# FMC_and_Power.net
KiCad netlist of a schematic drawn in Altium Designer
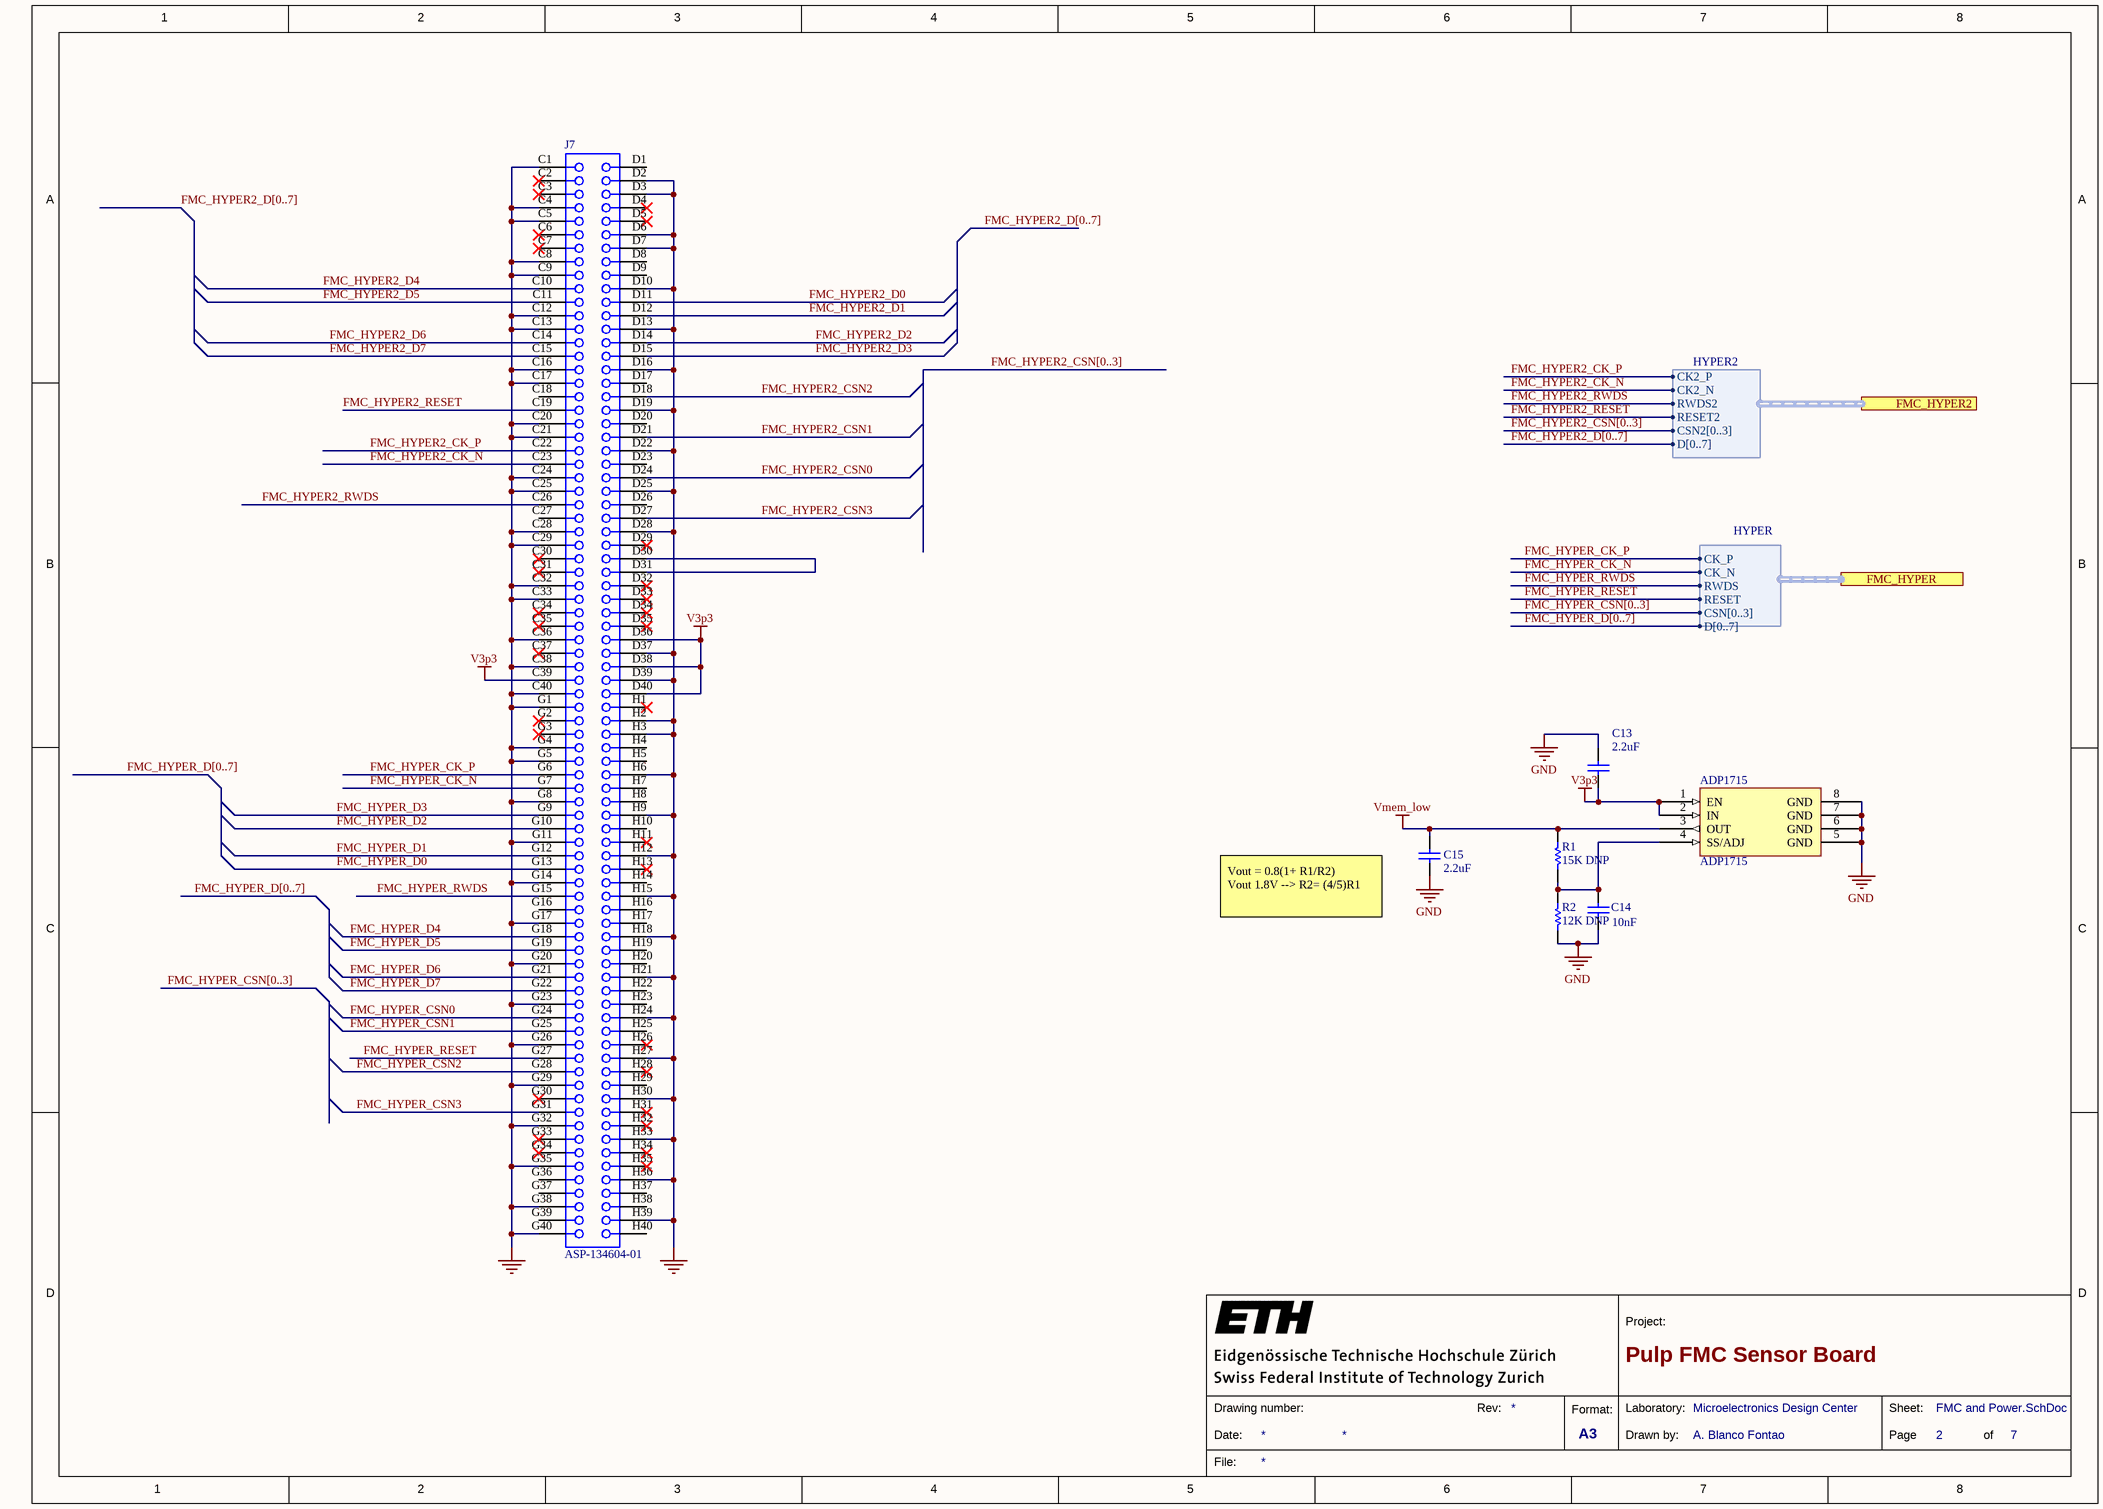
[diagram p0: FMC and Power.SchDoc]

(export (version "E")
  (design (tool "Eeschema 10.0.6"))
  (components
    (comp (ref "ADP1715")
      (value "ADP1715")
      (footprint "TSOP65P490X110-8N")
      (libsource (lib "ADP1715") (part "ADP1715"))
    )
    (comp (ref "C13")
      (value "2.2uF")
      (footprint "0402-A")
      (description "Capacitor (Semiconductor SIM Model)")
      (fields (field (name "Comment") "Cap Semi") (field (name "PUBLISHER") "Altium Limited"))
      (libsource (lib "Miscellaneous Devices") (part "Cap Semi"))
    )
    (comp (ref "C14")
      (value "10nF")
      (footprint "0402-A")
      (description "Capacitor (Semiconductor SIM Model)")
      (fields (field (name "Comment") "Cap Semi") (field (name "PUBLISHER") "Altium Limited"))
      (libsource (lib "Miscellaneous Devices") (part "Cap Semi"))
    )
    (comp (ref "C15")
      (value "2.2uF")
      (footprint "0402-A")
      (description "Capacitor (Semiconductor SIM Model)")
      (fields (field (name "Comment") "Cap Semi") (field (name "PUBLISHER") "Altium Limited"))
      (libsource (lib "Miscellaneous Devices") (part "Cap Semi"))
    )
    (comp (ref "J7")
      (value "ASP-134604-01")
      (footprint "ASP-134604-01")
      (description "Conn Array Terminal FMC Male SKT 160 POS 1.27mm Solder ST SMD")
      (fields (field (name "MANUFACTURER") "Samtec"))
      (libsource (lib "ETHZ Vault") (part "ASP-134604-01"))
    )
    (comp (ref "R1")
      (value "15K DNP")
      (footprint "RESC0603(1608)_N")
      (description "15K 0.1W 5% 0603 (1608 Metric)  SMD")
      (fields (field (name "TOLERANCE") "5 %") (field (name "POWER") "0.1 W"))
      (libsource (lib "Altium Content Vault") (part "CMP-1012-00098-1"))
    )
    (comp (ref "R2")
      (value "12K DNP")
      (footprint "RESC0603(1608)_N")
      (description "12K 0.1W 5% 0603 (1608 Metric)  SMD")
      (fields (field (name "TOLERANCE") "5 %") (field (name "POWER") "0.1 W"))
      (libsource (lib "Altium Content Vault") (part "CMP-1012-00098-1"))
    )
  )
  (nets
    (net (code "3") (name "/FMC_HYPER2_CK_N") (class "Default")
      (node (ref "J7") (pin "C23") (pinfunction "C23_C23") (pintype "passive"))
    )
    (net (code "4") (name "/FMC_HYPER2_CK_P") (class "Default")
      (node (ref "J7") (pin "C22") (pinfunction "C22_C22") (pintype "passive"))
    )
    (net (code "5") (name "/FMC_HYPER2_CSN0") (class "Default")
      (node (ref "J7") (pin "D24") (pinfunction "D24_D24") (pintype "passive"))
    )
    (net (code "6") (name "/FMC_HYPER2_CSN1") (class "Default")
      (node (ref "J7") (pin "D21") (pinfunction "D21_D21") (pintype "passive"))
    )
    (net (code "7") (name "/FMC_HYPER2_CSN2") (class "Default")
      (node (ref "J7") (pin "D18") (pinfunction "D18_D18") (pintype "passive"))
    )
    (net (code "8") (name "/FMC_HYPER2_CSN3") (class "Default")
      (node (ref "J7") (pin "D27") (pinfunction "D27_D27") (pintype "passive"))
    )
    (net (code "10") (name "/FMC_HYPER2_D0") (class "Default")
      (node (ref "J7") (pin "D11") (pinfunction "D11_D11") (pintype "passive"))
    )
    (net (code "11") (name "/FMC_HYPER2_D1") (class "Default")
      (node (ref "J7") (pin "D12") (pinfunction "D12_D12") (pintype "passive"))
    )
    (net (code "12") (name "/FMC_HYPER2_D2") (class "Default")
      (node (ref "J7") (pin "D14") (pinfunction "D14_D14") (pintype "passive"))
    )
    (net (code "13") (name "/FMC_HYPER2_D3") (class "Default")
      (node (ref "J7") (pin "D15") (pinfunction "D15_D15") (pintype "passive"))
    )
    (net (code "14") (name "/FMC_HYPER2_D4") (class "Default")
      (node (ref "J7") (pin "C10") (pinfunction "C10_C10") (pintype "passive"))
    )
    (net (code "15") (name "/FMC_HYPER2_D5") (class "Default")
      (node (ref "J7") (pin "C11") (pinfunction "C11_C11") (pintype "passive"))
    )
    (net (code "16") (name "/FMC_HYPER2_D6") (class "Default")
      (node (ref "J7") (pin "C14") (pinfunction "C14_C14") (pintype "passive"))
    )
    (net (code "17") (name "/FMC_HYPER2_D7") (class "Default")
      (node (ref "J7") (pin "C15") (pinfunction "C15_C15") (pintype "passive"))
    )
    (net (code "19") (name "/FMC_HYPER2_RESET") (class "Default")
      (node (ref "J7") (pin "C19") (pinfunction "C19_C19") (pintype "passive"))
    )
    (net (code "20") (name "/FMC_HYPER2_RWDS") (class "Default")
      (node (ref "J7") (pin "C26") (pinfunction "C26_C26") (pintype "passive"))
    )
    (net (code "22") (name "/FMC_HYPER_CK_N") (class "Default")
      (node (ref "J7") (pin "G7") (pinfunction "G7_G7") (pintype "passive"))
    )
    (net (code "23") (name "/FMC_HYPER_CK_P") (class "Default")
      (node (ref "J7") (pin "G6") (pinfunction "G6_G6") (pintype "passive"))
    )
    (net (code "24") (name "/FMC_HYPER_CSN0") (class "Default")
      (node (ref "J7") (pin "G24") (pinfunction "G24_G24") (pintype "passive"))
    )
    (net (code "25") (name "/FMC_HYPER_CSN1") (class "Default")
      (node (ref "J7") (pin "G25") (pinfunction "G25_G25") (pintype "passive"))
    )
    (net (code "26") (name "/FMC_HYPER_CSN2") (class "Default")
      (node (ref "J7") (pin "G28") (pinfunction "G28_G28") (pintype "passive"))
    )
    (net (code "27") (name "/FMC_HYPER_CSN3") (class "Default")
      (node (ref "J7") (pin "G31") (pinfunction "G31_G31") (pintype "passive"))
    )
    (net (code "29") (name "/FMC_HYPER_D0") (class "Default")
      (node (ref "J7") (pin "G13") (pinfunction "G13_G13") (pintype "passive"))
    )
    (net (code "30") (name "/FMC_HYPER_D1") (class "Default")
      (node (ref "J7") (pin "G12") (pinfunction "G12_G12") (pintype "passive"))
    )
    (net (code "31") (name "/FMC_HYPER_D2") (class "Default")
      (node (ref "J7") (pin "G10") (pinfunction "G10_G10") (pintype "passive"))
    )
    (net (code "32") (name "/FMC_HYPER_D3") (class "Default")
      (node (ref "J7") (pin "G9") (pinfunction "G9_G9") (pintype "passive"))
    )
    (net (code "33") (name "/FMC_HYPER_D4") (class "Default")
      (node (ref "J7") (pin "G18") (pinfunction "G18_G18") (pintype "passive"))
    )
    (net (code "34") (name "/FMC_HYPER_D5") (class "Default")
      (node (ref "J7") (pin "G19") (pinfunction "G19_G19") (pintype "passive"))
    )
    (net (code "35") (name "/FMC_HYPER_D6") (class "Default")
      (node (ref "J7") (pin "G21") (pinfunction "G21_G21") (pintype "passive"))
    )
    (net (code "36") (name "/FMC_HYPER_D7") (class "Default")
      (node (ref "J7") (pin "G22") (pinfunction "G22_G22") (pintype "passive"))
    )
    (net (code "38") (name "/FMC_HYPER_RESET") (class "Default")
      (node (ref "J7") (pin "G27") (pinfunction "G27_G27") (pintype "passive"))
    )
    (net (code "39") (name "/FMC_HYPER_RWDS") (class "Default")
      (node (ref "J7") (pin "G15") (pinfunction "G15_G15") (pintype "passive"))
    )
    (net (code "43") (name "GND") (class "Default")
      (node (ref "ADP1715") (pin "5") (pinfunction "GND_5") (pintype "power_in"))
      (node (ref "ADP1715") (pin "6") (pinfunction "GND_6") (pintype "power_in"))
      (node (ref "ADP1715") (pin "7") (pinfunction "GND_7") (pintype "power_in"))
      (node (ref "ADP1715") (pin "8") (pinfunction "GND_8") (pintype "power_in"))
      (node (ref "C13") (pin "1") (pinfunction "1_1") (pintype "passive"))
      (node (ref "C14") (pin "2") (pinfunction "2_2") (pintype "passive"))
      (node (ref "C15") (pin "2") (pinfunction "2_2") (pintype "passive"))
      (node (ref "J7") (pin "C1") (pinfunction "C1_C1") (pintype "passive"))
      (node (ref "J7") (pin "C12") (pinfunction "C12_C12") (pintype "passive"))
      (node (ref "J7") (pin "C13") (pinfunction "C13_C13") (pintype "passive"))
      (node (ref "J7") (pin "C16") (pinfunction "C16_C16") (pintype "passive"))
      (node (ref "J7") (pin "C17") (pinfunction "C17_C17") (pintype "passive"))
      (node (ref "J7") (pin "C20") (pinfunction "C20_C20") (pintype "passive"))
      (node (ref "J7") (pin "C21") (pinfunction "C21_C21") (pintype "passive"))
      (node (ref "J7") (pin "C24") (pinfunction "C24_C24") (pintype "passive"))
      (node (ref "J7") (pin "C25") (pinfunction "C25_C25") (pintype "passive"))
      (node (ref "J7") (pin "C28") (pinfunction "C28_C28") (pintype "passive"))
      (node (ref "J7") (pin "C29") (pinfunction "C29_C29") (pintype "passive"))
      (node (ref "J7") (pin "C32") (pinfunction "C32_C32") (pintype "passive"))
      (node (ref "J7") (pin "C33") (pinfunction "C33_C33") (pintype "passive"))
      (node (ref "J7") (pin "C36") (pinfunction "C36_C36") (pintype "passive"))
      (node (ref "J7") (pin "C38") (pinfunction "C38_C38") (pintype "passive"))
      (node (ref "J7") (pin "C4") (pinfunction "C4_C4") (pintype "passive"))
      (node (ref "J7") (pin "C40") (pinfunction "C40_C40") (pintype "passive"))
      (node (ref "J7") (pin "C5") (pinfunction "C5_C5") (pintype "passive"))
      (node (ref "J7") (pin "C8") (pinfunction "C8_C8") (pintype "passive"))
      (node (ref "J7") (pin "C9") (pinfunction "C9_C9") (pintype "passive"))
      (node (ref "J7") (pin "D10") (pinfunction "D10_D10") (pintype "passive"))
      (node (ref "J7") (pin "D13") (pinfunction "D13_D13") (pintype "passive"))
      (node (ref "J7") (pin "D16") (pinfunction "D16_D16") (pintype "passive"))
      (node (ref "J7") (pin "D19") (pinfunction "D19_D19") (pintype "passive"))
      (node (ref "J7") (pin "D2") (pinfunction "D2_D2") (pintype "passive"))
      (node (ref "J7") (pin "D22") (pinfunction "D22_D22") (pintype "passive"))
      (node (ref "J7") (pin "D25") (pinfunction "D25_D25") (pintype "passive"))
      (node (ref "J7") (pin "D28") (pinfunction "D28_D28") (pintype "passive"))
      (node (ref "J7") (pin "D3") (pinfunction "D3_D3") (pintype "passive"))
      (node (ref "J7") (pin "D37") (pinfunction "D37_D37") (pintype "passive"))
      (node (ref "J7") (pin "D39") (pinfunction "D39_D39") (pintype "passive"))
      (node (ref "J7") (pin "D6") (pinfunction "D6_D6") (pintype "passive"))
      (node (ref "J7") (pin "D7") (pinfunction "D7_D7") (pintype "passive"))
      (node (ref "J7") (pin "G1") (pinfunction "G1_G1") (pintype "passive"))
      (node (ref "J7") (pin "G11") (pinfunction "G11_G11") (pintype "passive"))
      (node (ref "J7") (pin "G14") (pinfunction "G14_G14") (pintype "passive"))
      (node (ref "J7") (pin "G17") (pinfunction "G17_G17") (pintype "passive"))
      (node (ref "J7") (pin "G20") (pinfunction "G20_G20") (pintype "passive"))
      (node (ref "J7") (pin "G23") (pinfunction "G23_G23") (pintype "passive"))
      (node (ref "J7") (pin "G26") (pinfunction "G26_G26") (pintype "passive"))
      (node (ref "J7") (pin "G29") (pinfunction "G29_G29") (pintype "passive"))
      (node (ref "J7") (pin "G32") (pinfunction "G32_G32") (pintype "passive"))
      (node (ref "J7") (pin "G35") (pinfunction "G35_G35") (pintype "passive"))
      (node (ref "J7") (pin "G38") (pinfunction "G38_G38") (pintype "passive"))
      (node (ref "J7") (pin "G4") (pinfunction "G4_G4") (pintype "passive"))
      (node (ref "J7") (pin "G40") (pinfunction "G40_G40") (pintype "passive"))
      (node (ref "J7") (pin "G5") (pinfunction "G5_G5") (pintype "passive"))
      (node (ref "J7") (pin "G8") (pinfunction "G8_G8") (pintype "passive"))
      (node (ref "J7") (pin "H12") (pinfunction "H12_H12") (pintype "passive"))
      (node (ref "J7") (pin "H15") (pinfunction "H15_H15") (pintype "passive"))
      (node (ref "J7") (pin "H18") (pinfunction "H18_H18") (pintype "passive"))
      (node (ref "J7") (pin "H2") (pinfunction "H2_H2") (pintype "passive"))
      (node (ref "J7") (pin "H21") (pinfunction "H21_H21") (pintype "passive"))
      (node (ref "J7") (pin "H24") (pinfunction "H24_H24") (pintype "passive"))
      (node (ref "J7") (pin "H27") (pinfunction "H27_H27") (pintype "passive"))
      (node (ref "J7") (pin "H3") (pinfunction "H3_H3") (pintype "passive"))
      (node (ref "J7") (pin "H30") (pinfunction "H30_H30") (pintype "passive"))
      (node (ref "J7") (pin "H33") (pinfunction "H33_H33") (pintype "passive"))
      (node (ref "J7") (pin "H36") (pinfunction "H36_H36") (pintype "passive"))
      (node (ref "J7") (pin "H39") (pinfunction "H39_H39") (pintype "passive"))
      (node (ref "J7") (pin "H6") (pinfunction "H6_H6") (pintype "passive"))
      (node (ref "J7") (pin "H9") (pinfunction "H9_H9") (pintype "passive"))
      (node (ref "R2") (pin "1") (pinfunction "1_1") (pintype "passive"))
    )
    (net (code "44") (name "Net-(ADP1715-SS{slash}ADJ)") (class "Default")
      (node (ref "ADP1715") (pin "4") (pinfunction "SS/ADJ_4") (pintype "input"))
      (node (ref "C14") (pin "1") (pinfunction "1_1") (pintype "passive"))
      (node (ref "R1") (pin "1") (pinfunction "1_1") (pintype "passive"))
      (node (ref "R2") (pin "2") (pinfunction "2_2") (pintype "passive"))
    )
    (net (code "45") (name "Net-(J7-PadD30)") (class "Default")
      (node (ref "J7") (pin "D30") (pinfunction "D30_D30") (pintype "passive"))
      (node (ref "J7") (pin "D31") (pinfunction "D31_D31") (pintype "passive"))
    )
    (net (code "46") (name "V3p3") (class "Default")
      (node (ref "ADP1715") (pin "1") (pinfunction "EN_1") (pintype "input"))
      (node (ref "ADP1715") (pin "2") (pinfunction "IN_2") (pintype "input"))
      (node (ref "C13") (pin "2") (pinfunction "2_2") (pintype "passive"))
      (node (ref "J7") (pin "C39") (pinfunction "C39_C39") (pintype "passive"))
      (node (ref "J7") (pin "D36") (pinfunction "D36_D36") (pintype "passive"))
      (node (ref "J7") (pin "D38") (pinfunction "D38_D38") (pintype "passive"))
      (node (ref "J7") (pin "D40") (pinfunction "D40_D40") (pintype "passive"))
    )
    (net (code "47") (name "Vmem_low") (class "Default")
      (node (ref "ADP1715") (pin "3") (pinfunction "OUT_3") (pintype "output"))
      (node (ref "C15") (pin "1") (pinfunction "1_1") (pintype "passive"))
      (node (ref "R1") (pin "2") (pinfunction "2_2") (pintype "passive"))
    )
    (net (code "48") (name "unconnected-(J7-PadC2)") (class "Default")
      (node (ref "J7") (pin "C2") (pinfunction "C2_C2") (pintype "passive+no_connect"))
    )
    (net (code "49") (name "unconnected-(J7-PadC3)") (class "Default")
      (node (ref "J7") (pin "C3") (pinfunction "C3_C3") (pintype "passive+no_connect"))
    )
    (net (code "50") (name "unconnected-(J7-PadC6)") (class "Default")
      (node (ref "J7") (pin "C6") (pinfunction "C6_C6") (pintype "passive+no_connect"))
    )
    (net (code "51") (name "unconnected-(J7-PadC7)") (class "Default")
      (node (ref "J7") (pin "C7") (pinfunction "C7_C7") (pintype "passive+no_connect"))
    )
    (net (code "52") (name "unconnected-(J7-PadC18)") (class "Default")
      (node (ref "J7") (pin "C18") (pinfunction "C18_C18") (pintype "passive"))
    )
    (net (code "53") (name "unconnected-(J7-PadC27)") (class "Default")
      (node (ref "J7") (pin "C27") (pinfunction "C27_C27") (pintype "passive"))
    )
    (net (code "54") (name "unconnected-(J7-PadC30)") (class "Default")
      (node (ref "J7") (pin "C30") (pinfunction "C30_C30") (pintype "passive+no_connect"))
    )
    (net (code "55") (name "unconnected-(J7-PadC31)") (class "Default")
      (node (ref "J7") (pin "C31") (pinfunction "C31_C31") (pintype "passive+no_connect"))
    )
    (net (code "56") (name "unconnected-(J7-PadC34)") (class "Default")
      (node (ref "J7") (pin "C34") (pinfunction "C34_C34") (pintype "passive+no_connect"))
    )
    (net (code "57") (name "unconnected-(J7-PadC35)") (class "Default")
      (node (ref "J7") (pin "C35") (pinfunction "C35_C35") (pintype "passive+no_connect"))
    )
    (net (code "58") (name "unconnected-(J7-PadC37)") (class "Default")
      (node (ref "J7") (pin "C37") (pinfunction "C37_C37") (pintype "passive+no_connect"))
    )
    (net (code "59") (name "unconnected-(J7-PadD1)") (class "Default")
      (node (ref "J7") (pin "D1") (pinfunction "D1_D1") (pintype "passive"))
    )
    (net (code "60") (name "unconnected-(J7-PadD4)") (class "Default")
      (node (ref "J7") (pin "D4") (pinfunction "D4_D4") (pintype "passive+no_connect"))
    )
    (net (code "61") (name "unconnected-(J7-PadD5)") (class "Default")
      (node (ref "J7") (pin "D5") (pinfunction "D5_D5") (pintype "passive+no_connect"))
    )
    (net (code "62") (name "unconnected-(J7-PadD8)") (class "Default")
      (node (ref "J7") (pin "D8") (pinfunction "D8_D8") (pintype "passive"))
    )
    (net (code "63") (name "unconnected-(J7-PadD9)") (class "Default")
      (node (ref "J7") (pin "D9") (pinfunction "D9_D9") (pintype "passive"))
    )
    (net (code "64") (name "unconnected-(J7-PadD17)") (class "Default")
      (node (ref "J7") (pin "D17") (pinfunction "D17_D17") (pintype "passive"))
    )
    (net (code "65") (name "unconnected-(J7-PadD20)") (class "Default")
      (node (ref "J7") (pin "D20") (pinfunction "D20_D20") (pintype "passive"))
    )
    (net (code "66") (name "unconnected-(J7-PadD23)") (class "Default")
      (node (ref "J7") (pin "D23") (pinfunction "D23_D23") (pintype "passive"))
    )
    (net (code "67") (name "unconnected-(J7-PadD26)") (class "Default")
      (node (ref "J7") (pin "D26") (pinfunction "D26_D26") (pintype "passive"))
    )
    (net (code "68") (name "unconnected-(J7-PadD29)") (class "Default")
      (node (ref "J7") (pin "D29") (pinfunction "D29_D29") (pintype "passive+no_connect"))
    )
    (net (code "69") (name "unconnected-(J7-PadD32)") (class "Default")
      (node (ref "J7") (pin "D32") (pinfunction "D32_D32") (pintype "passive+no_connect"))
    )
    (net (code "70") (name "unconnected-(J7-PadD33)") (class "Default")
      (node (ref "J7") (pin "D33") (pinfunction "D33_D33") (pintype "passive+no_connect"))
    )
    (net (code "71") (name "unconnected-(J7-PadD34)") (class "Default")
      (node (ref "J7") (pin "D34") (pinfunction "D34_D34") (pintype "passive+no_connect"))
    )
    (net (code "72") (name "unconnected-(J7-PadD35)") (class "Default")
      (node (ref "J7") (pin "D35") (pinfunction "D35_D35") (pintype "passive+no_connect"))
    )
    (net (code "73") (name "unconnected-(J7-PadG2)") (class "Default")
      (node (ref "J7") (pin "G2") (pinfunction "G2_G2") (pintype "passive+no_connect"))
    )
    (net (code "74") (name "unconnected-(J7-PadG3)") (class "Default")
      (node (ref "J7") (pin "G3") (pinfunction "G3_G3") (pintype "passive+no_connect"))
    )
    (net (code "75") (name "unconnected-(J7-PadG16)") (class "Default")
      (node (ref "J7") (pin "G16") (pinfunction "G16_G16") (pintype "passive"))
    )
    (net (code "76") (name "unconnected-(J7-PadG30)") (class "Default")
      (node (ref "J7") (pin "G30") (pinfunction "G30_G30") (pintype "passive+no_connect"))
    )
    (net (code "77") (name "unconnected-(J7-PadG33)") (class "Default")
      (node (ref "J7") (pin "G33") (pinfunction "G33_G33") (pintype "passive+no_connect"))
    )
    (net (code "78") (name "unconnected-(J7-PadG34)") (class "Default")
      (node (ref "J7") (pin "G34") (pinfunction "G34_G34") (pintype "passive+no_connect"))
    )
    (net (code "79") (name "unconnected-(J7-PadG36)") (class "Default")
      (node (ref "J7") (pin "G36") (pinfunction "G36_G36") (pintype "passive"))
    )
    (net (code "80") (name "unconnected-(J7-PadG37)") (class "Default")
      (node (ref "J7") (pin "G37") (pinfunction "G37_G37") (pintype "passive"))
    )
    (net (code "81") (name "unconnected-(J7-PadG39)") (class "Default")
      (node (ref "J7") (pin "G39") (pinfunction "G39_G39") (pintype "passive"))
    )
    (net (code "82") (name "unconnected-(J7-PadH1)") (class "Default")
      (node (ref "J7") (pin "H1") (pinfunction "H1_H1") (pintype "passive+no_connect"))
    )
    (net (code "83") (name "unconnected-(J7-PadH4)") (class "Default")
      (node (ref "J7") (pin "H4") (pinfunction "H4_H4") (pintype "passive"))
    )
    (net (code "84") (name "unconnected-(J7-PadH5)") (class "Default")
      (node (ref "J7") (pin "H5") (pinfunction "H5_H5") (pintype "passive"))
    )
    (net (code "85") (name "unconnected-(J7-PadH7)") (class "Default")
      (node (ref "J7") (pin "H7") (pinfunction "H7_H7") (pintype "passive"))
    )
    (net (code "86") (name "unconnected-(J7-PadH8)") (class "Default")
      (node (ref "J7") (pin "H8") (pinfunction "H8_H8") (pintype "passive"))
    )
    (net (code "87") (name "unconnected-(J7-PadH10)") (class "Default")
      (node (ref "J7") (pin "H10") (pinfunction "H10_H10") (pintype "passive"))
    )
    (net (code "88") (name "unconnected-(J7-PadH11)") (class "Default")
      (node (ref "J7") (pin "H11") (pinfunction "H11_H11") (pintype "passive+no_connect"))
    )
    (net (code "89") (name "unconnected-(J7-PadH13)") (class "Default")
      (node (ref "J7") (pin "H13") (pinfunction "H13_H13") (pintype "passive+no_connect"))
    )
    (net (code "90") (name "unconnected-(J7-PadH14)") (class "Default")
      (node (ref "J7") (pin "H14") (pinfunction "H14_H14") (pintype "passive"))
    )
    (net (code "91") (name "unconnected-(J7-PadH16)") (class "Default")
      (node (ref "J7") (pin "H16") (pinfunction "H16_H16") (pintype "passive"))
    )
    (net (code "92") (name "unconnected-(J7-PadH17)") (class "Default")
      (node (ref "J7") (pin "H17") (pinfunction "H17_H17") (pintype "passive"))
    )
    (net (code "93") (name "unconnected-(J7-PadH19)") (class "Default")
      (node (ref "J7") (pin "H19") (pinfunction "H19_H19") (pintype "passive"))
    )
    (net (code "94") (name "unconnected-(J7-PadH20)") (class "Default")
      (node (ref "J7") (pin "H20") (pinfunction "H20_H20") (pintype "passive"))
    )
    (net (code "95") (name "unconnected-(J7-PadH22)") (class "Default")
      (node (ref "J7") (pin "H22") (pinfunction "H22_H22") (pintype "passive"))
    )
    (net (code "96") (name "unconnected-(J7-PadH23)") (class "Default")
      (node (ref "J7") (pin "H23") (pinfunction "H23_H23") (pintype "passive"))
    )
    (net (code "97") (name "unconnected-(J7-PadH25)") (class "Default")
      (node (ref "J7") (pin "H25") (pinfunction "H25_H25") (pintype "passive"))
    )
    (net (code "98") (name "unconnected-(J7-PadH26)") (class "Default")
      (node (ref "J7") (pin "H26") (pinfunction "H26_H26") (pintype "passive+no_connect"))
    )
    (net (code "99") (name "unconnected-(J7-PadH28)") (class "Default")
      (node (ref "J7") (pin "H28") (pinfunction "H28_H28") (pintype "passive+no_connect"))
    )
    (net (code "100") (name "unconnected-(J7-PadH29)") (class "Default")
      (node (ref "J7") (pin "H29") (pinfunction "H29_H29") (pintype "passive"))
    )
    (net (code "101") (name "unconnected-(J7-PadH31)") (class "Default")
      (node (ref "J7") (pin "H31") (pinfunction "H31_H31") (pintype "passive+no_connect"))
    )
    (net (code "102") (name "unconnected-(J7-PadH32)") (class "Default")
      (node (ref "J7") (pin "H32") (pinfunction "H32_H32") (pintype "passive+no_connect"))
    )
    (net (code "103") (name "unconnected-(J7-PadH34)") (class "Default")
      (node (ref "J7") (pin "H34") (pinfunction "H34_H34") (pintype "passive+no_connect"))
    )
    (net (code "104") (name "unconnected-(J7-PadH35)") (class "Default")
      (node (ref "J7") (pin "H35") (pinfunction "H35_H35") (pintype "passive+no_connect"))
    )
    (net (code "105") (name "unconnected-(J7-PadH37)") (class "Default")
      (node (ref "J7") (pin "H37") (pinfunction "H37_H37") (pintype "passive"))
    )
    (net (code "106") (name "unconnected-(J7-PadH38)") (class "Default")
      (node (ref "J7") (pin "H38") (pinfunction "H38_H38") (pintype "passive"))
    )
    (net (code "107") (name "unconnected-(J7-PadH40)") (class "Default")
      (node (ref "J7") (pin "H40") (pinfunction "H40_H40") (pintype "passive"))
    )
  )
)
